# MCU.net
KiCad netlist of a schematic drawn in Altium Designer
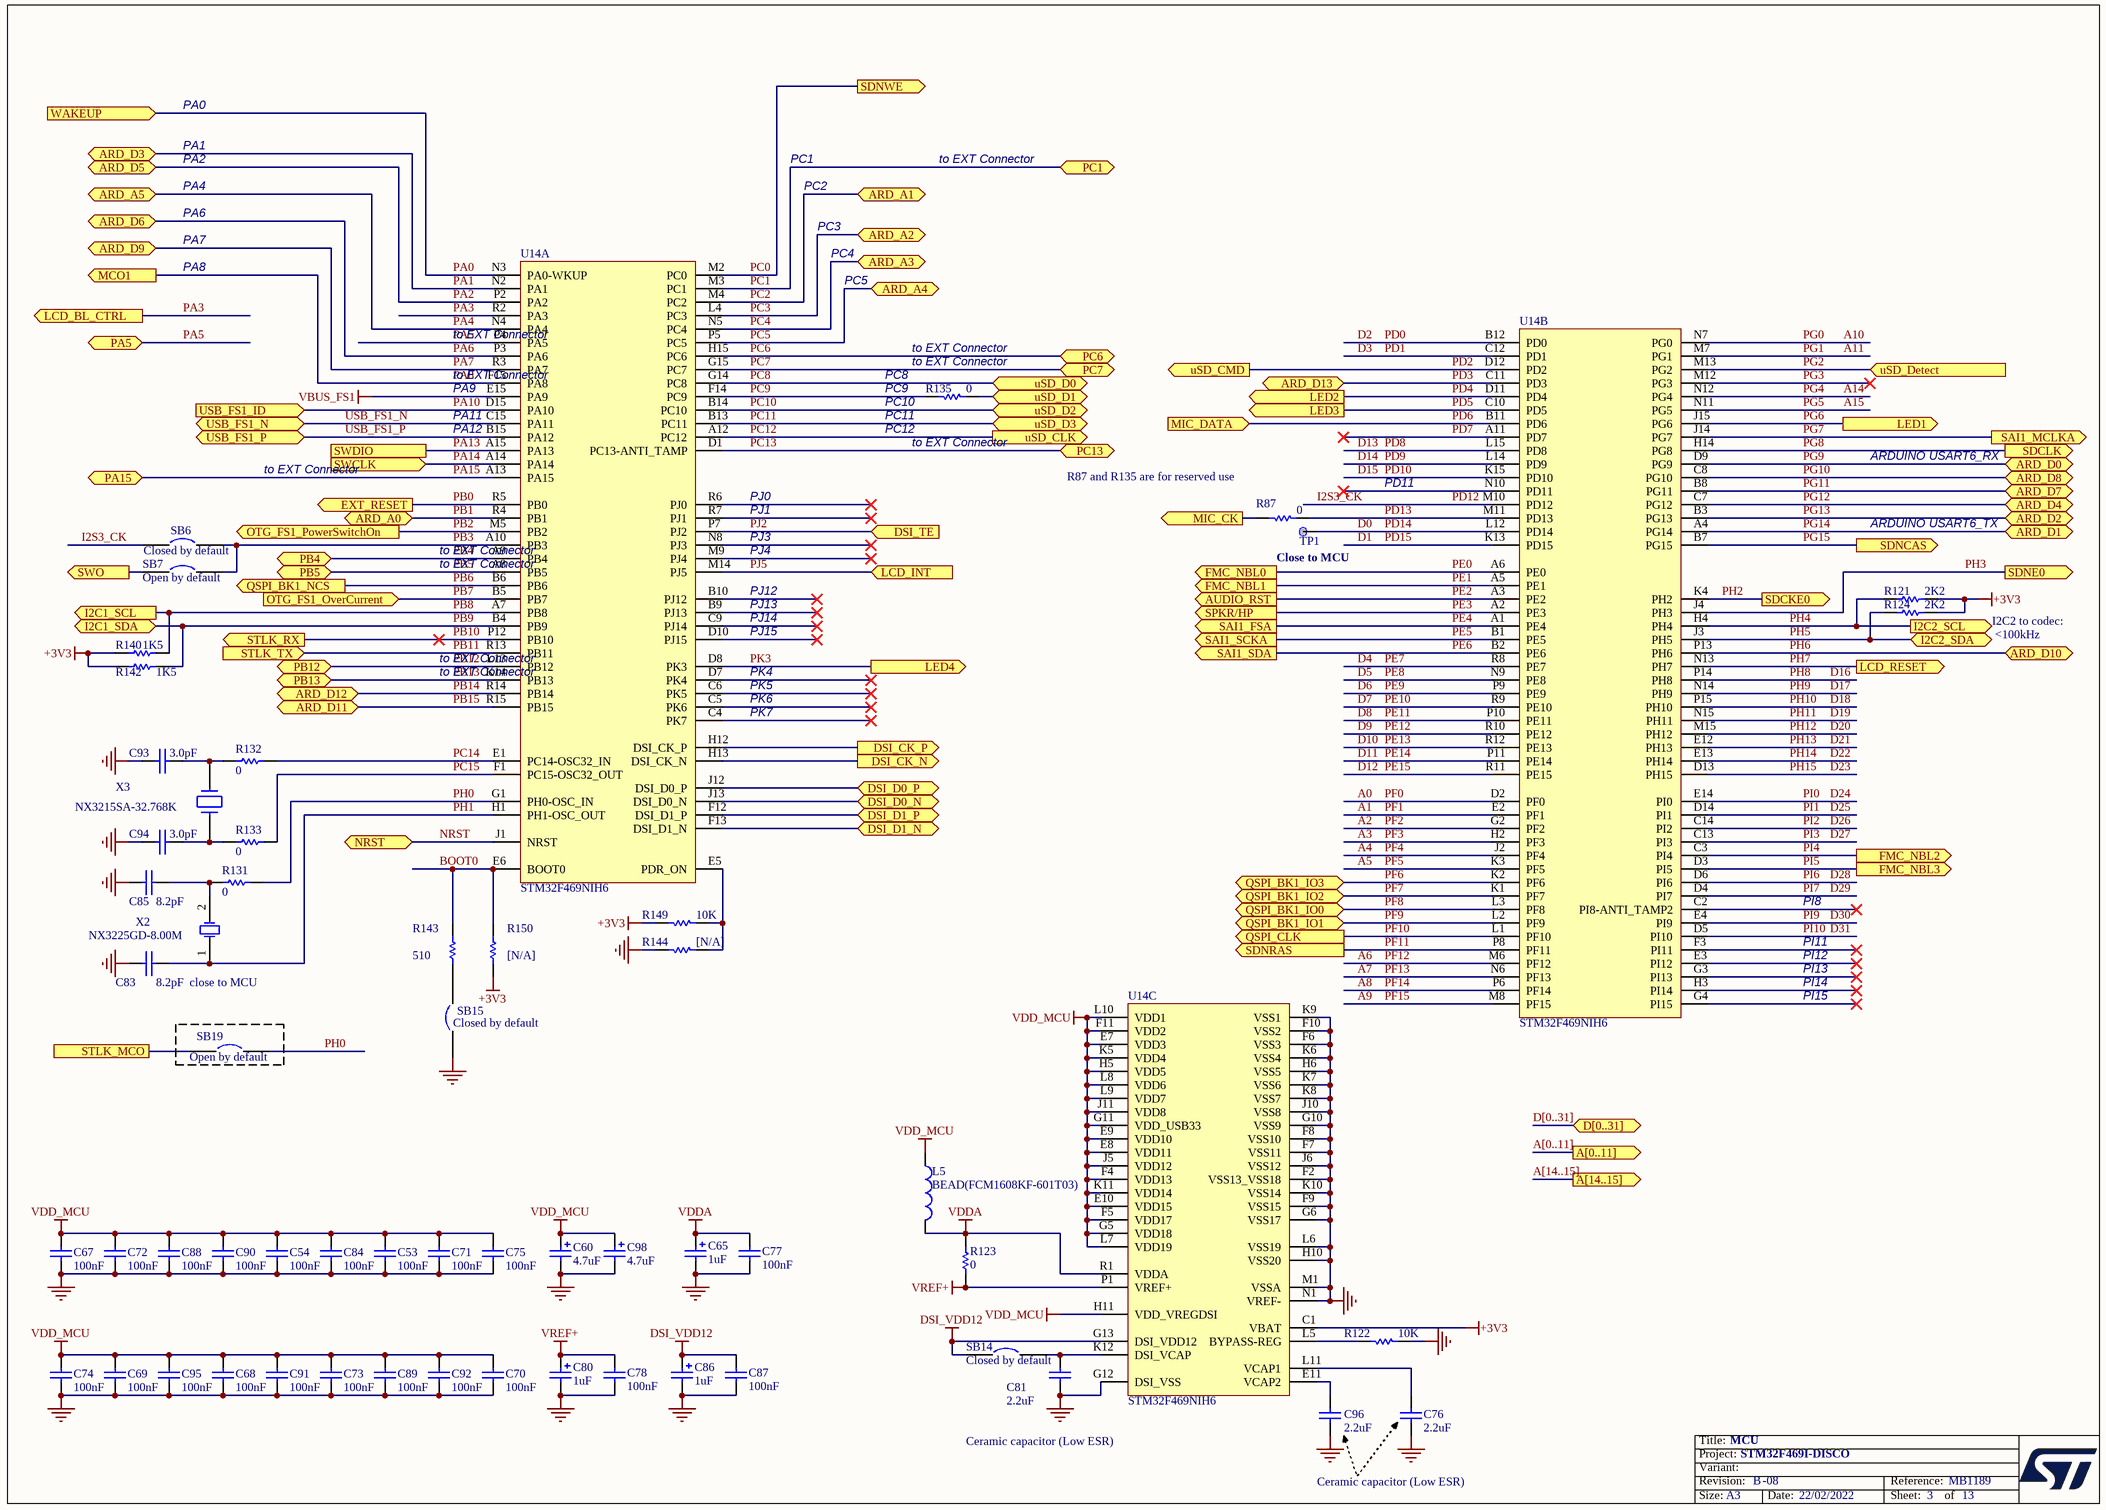
[diagram p0: MCU.SchDoc]

(export (version "E")
  (design (tool "Eeschema 10.0.6"))
  (components
    (comp (ref "C53")
      (value "100nF")
      (footprint "0402C")
      (description "Capacitor")
      (fields (field (name "PUBLISHER") "Altium Limited"))
      (libsource (lib "Miscellaneous Devices") (part "CAP"))
    )
    (comp (ref "C54")
      (value "100nF")
      (footprint "0402C")
      (description "Capacitor")
      (fields (field (name "PUBLISHER") "Altium Limited"))
      (libsource (lib "Miscellaneous Devices") (part "CAP"))
    )
    (comp (ref "C60")
      (value "4.7uF")
      (footprint "TAN-A")
      (description "Polarized Capacitor (Radial)")
      (fields (field (name "PUBLISHER") "Altium Limited"))
      (libsource (lib "Miscellaneous Devices") (part "Cap Pol1"))
    )
    (comp (ref "C65")
      (value "1uF")
      (footprint "TAN-A")
      (description "Polarized Capacitor (Radial)")
      (fields (field (name "PUBLISHER") "Altium Limited"))
      (libsource (lib "Miscellaneous Devices") (part "Cap Pol1"))
    )
    (comp (ref "C67")
      (value "100nF")
      (footprint "0402C")
      (description "Capacitor")
      (fields (field (name "PUBLISHER") "Altium Limited"))
      (libsource (lib "Miscellaneous Devices") (part "CAP"))
    )
    (comp (ref "C68")
      (value "100nF")
      (footprint "0402C")
      (description "Capacitor")
      (fields (field (name "PUBLISHER") "Altium Limited"))
      (libsource (lib "Miscellaneous Devices") (part "CAP"))
    )
    (comp (ref "C69")
      (value "100nF")
      (footprint "0402C")
      (description "Capacitor")
      (fields (field (name "PUBLISHER") "Altium Limited"))
      (libsource (lib "Miscellaneous Devices") (part "CAP"))
    )
    (comp (ref "C70")
      (value "100nF")
      (footprint "0402C")
      (description "Capacitor")
      (fields (field (name "PUBLISHER") "Altium Limited"))
      (libsource (lib "Miscellaneous Devices") (part "CAP"))
    )
    (comp (ref "C71")
      (value "100nF")
      (footprint "0402C")
      (description "Capacitor")
      (fields (field (name "PUBLISHER") "Altium Limited"))
      (libsource (lib "Miscellaneous Devices") (part "CAP"))
    )
    (comp (ref "C72")
      (value "100nF")
      (footprint "0402C")
      (description "Capacitor")
      (fields (field (name "PUBLISHER") "Altium Limited"))
      (libsource (lib "Miscellaneous Devices") (part "CAP"))
    )
    (comp (ref "C73")
      (value "100nF")
      (footprint "0402C")
      (description "Capacitor")
      (fields (field (name "PUBLISHER") "Altium Limited"))
      (libsource (lib "Miscellaneous Devices") (part "CAP"))
    )
    (comp (ref "C74")
      (value "100nF")
      (footprint "0402C")
      (description "Capacitor")
      (fields (field (name "PUBLISHER") "Altium Limited"))
      (libsource (lib "Miscellaneous Devices") (part "CAP"))
    )
    (comp (ref "C75")
      (value "100nF")
      (footprint "0402C")
      (description "Capacitor")
      (fields (field (name "PUBLISHER") "Altium Limited"))
      (libsource (lib "Miscellaneous Devices") (part "CAP"))
    )
    (comp (ref "C76")
      (value "2.2uF")
      (footprint "1206C")
      (description "Capacitor")
      (fields (field (name "PUBLISHER") "Altium Limited"))
      (libsource (lib "Miscellaneous Devices") (part "Cap"))
    )
    (comp (ref "C77")
      (value "100nF")
      (footprint "0402C")
      (description "Capacitor")
      (fields (field (name "PUBLISHER") "Altium Limited"))
      (libsource (lib "Miscellaneous Devices") (part "Cap"))
    )
    (comp (ref "C78")
      (value "100nF")
      (footprint "0402C")
      (description "Capacitor")
      (fields (field (name "PUBLISHER") "Altium Limited"))
      (libsource (lib "Miscellaneous Devices") (part "Cap"))
    )
    (comp (ref "C80")
      (value "1uF")
      (footprint "TAN-A")
      (description "Polarized Capacitor (Radial)")
      (fields (field (name "PUBLISHER") "Altium Limited"))
      (libsource (lib "Miscellaneous Devices") (part "Cap Pol1"))
    )
    (comp (ref "C81")
      (value "2.2uF")
      (footprint "1206C")
      (description "Capacitor")
      (fields (field (name "PUBLISHER") "Altium Limited"))
      (libsource (lib "Miscellaneous Devices") (part "Cap"))
    )
    (comp (ref "C83")
      (value "8.2pF")
      (footprint "0603C")
      (description "Capacitor")
      (libsource (lib "*") (part "CAP"))
    )
    (comp (ref "C84")
      (value "100nF")
      (footprint "0402C")
      (description "Capacitor")
      (fields (field (name "PUBLISHER") "Altium Limited"))
      (libsource (lib "Miscellaneous Devices") (part "CAP"))
    )
    (comp (ref "C85")
      (value "8.2pF")
      (footprint "0603C")
      (description "Capacitor")
      (libsource (lib "*") (part "CAP"))
    )
    (comp (ref "C86")
      (value "1uF")
      (footprint "TAN-A")
      (description "Polarized Capacitor (Radial)")
      (fields (field (name "PUBLISHER") "Altium Limited"))
      (libsource (lib "Miscellaneous Devices") (part "Cap Pol1"))
    )
    (comp (ref "C87")
      (value "100nF")
      (footprint "0402C")
      (description "Capacitor")
      (fields (field (name "PUBLISHER") "Altium Limited"))
      (libsource (lib "Miscellaneous Devices") (part "Cap"))
    )
    (comp (ref "C88")
      (value "100nF")
      (footprint "0402C")
      (description "Capacitor")
      (fields (field (name "PUBLISHER") "Altium Limited"))
      (libsource (lib "Miscellaneous Devices") (part "CAP"))
    )
    (comp (ref "C89")
      (value "100nF")
      (footprint "0402C")
      (description "Capacitor")
      (fields (field (name "PUBLISHER") "Altium Limited"))
      (libsource (lib "Miscellaneous Devices") (part "CAP"))
    )
    (comp (ref "C90")
      (value "100nF")
      (footprint "0402C")
      (description "Capacitor")
      (fields (field (name "PUBLISHER") "Altium Limited"))
      (libsource (lib "Miscellaneous Devices") (part "CAP"))
    )
    (comp (ref "C91")
      (value "100nF")
      (footprint "0402C")
      (description "Capacitor")
      (fields (field (name "PUBLISHER") "Altium Limited"))
      (libsource (lib "Miscellaneous Devices") (part "CAP"))
    )
    (comp (ref "C92")
      (value "100nF")
      (footprint "0402C")
      (description "Capacitor")
      (fields (field (name "PUBLISHER") "Altium Limited"))
      (libsource (lib "Miscellaneous Devices") (part "CAP"))
    )
    (comp (ref "C93")
      (value "3.0pF")
      (footprint "0603C")
      (description "Capacitor")
      (libsource (lib "") (part "CAP_1"))
    )
    (comp (ref "C94")
      (value "3.0pF")
      (footprint "0603C")
      (description "Capacitor")
      (libsource (lib "") (part "CAP_1"))
    )
    (comp (ref "C95")
      (value "100nF")
      (footprint "0402C")
      (description "Capacitor")
      (fields (field (name "PUBLISHER") "Altium Limited"))
      (libsource (lib "Miscellaneous Devices") (part "CAP"))
    )
    (comp (ref "C96")
      (value "2.2uF")
      (footprint "1206C")
      (description "Capacitor")
      (fields (field (name "PUBLISHER") "Altium Limited"))
      (libsource (lib "Miscellaneous Devices") (part "Cap"))
    )
    (comp (ref "C98")
      (value "4.7uF")
      (footprint "TAN-A")
      (description "Polarized Capacitor (Radial)")
      (fields (field (name "PUBLISHER") "Altium Limited"))
      (libsource (lib "Miscellaneous Devices") (part "Cap Pol1"))
    )
    (comp (ref "L5")
      (value "BEAD(FCM1608KF-601T03)")
      (footprint "0603L")
      (description "Inductor")
      (fields (field (name "PUBLISHER") "Altium Limited"))
      (libsource (lib "Miscellaneous Devices") (part "Inductor"))
    )
    (comp (ref "R87")
      (value "0")
      (footprint "0603R")
      (description "Resistor")
      (fields (field (name "PUBLISHER") "Altium Limited"))
      (libsource (lib "Miscellaneous Devices") (part "Res1"))
    )
    (comp (ref "R121")
      (value "2K2")
      (footprint "0603R")
      (description "Resistor")
      (fields (field (name "PUBLISHER") "Altium Limited"))
      (libsource (lib "") (part "Res1_1"))
    )
    (comp (ref "R122")
      (value "10K")
      (footprint "0402R")
      (description "Resistor")
      (fields (field (name "PUBLISHER") "Altium Limited"))
      (libsource (lib "") (part "Res1_1"))
    )
    (comp (ref "R123")
      (value "0")
      (footprint "0603R")
      (description "Resistor")
      (fields (field (name "PUBLISHER") "Altium Limited"))
      (libsource (lib "Miscellaneous Devices") (part "Res1"))
    )
    (comp (ref "R124")
      (value "2K2")
      (footprint "0603R")
      (description "Resistor")
      (fields (field (name "PUBLISHER") "Altium Limited"))
      (libsource (lib "") (part "Res1_1"))
    )
    (comp (ref "R131")
      (value "0")
      (footprint "0603R")
      (description "Resistor")
      (fields (field (name "PUBLISHER") "Altium Limited"))
      (libsource (lib "Miscellaneous Devices") (part "Res1"))
    )
    (comp (ref "R132")
      (value "0")
      (footprint "0603R")
      (description "Resistor")
      (fields (field (name "PUBLISHER") "Altium Limited"))
      (libsource (lib "") (part "Res1_1"))
    )
    (comp (ref "R133")
      (value "0")
      (footprint "0603R")
      (description "Resistor")
      (fields (field (name "PUBLISHER") "Altium Limited"))
      (libsource (lib "") (part "Res1_1"))
    )
    (comp (ref "R135")
      (value "0")
      (footprint "0603R")
      (description "Resistor")
      (fields (field (name "PUBLISHER") "Altium Limited"))
      (libsource (lib "Miscellaneous Devices") (part "Res1"))
    )
    (comp (ref "R140")
      (value "1K5")
      (footprint "0603R")
      (description "Resistor")
      (fields (field (name "PUBLISHER") "Altium Limited"))
      (libsource (lib "") (part "Res1_1"))
    )
    (comp (ref "R142")
      (value "1K5")
      (footprint "0603R")
      (description "Resistor")
      (fields (field (name "PUBLISHER") "Altium Limited"))
      (libsource (lib "") (part "Res1_1"))
    )
    (comp (ref "R143")
      (value "510")
      (footprint "0603R")
      (description "Resistor")
      (fields (field (name "PUBLISHER") "Altium Limited"))
      (libsource (lib "Miscellaneous Devices") (part "res1"))
    )
    (comp (ref "R144")
      (value "[N/A]")
      (footprint "0603R")
      (description "Resistor")
      (fields (field (name "PUBLISHER") "Altium Limited"))
      (libsource (lib "Miscellaneous Devices") (part "Res1"))
    )
    (comp (ref "R149")
      (value "10K")
      (footprint "0402R")
      (description "Resistor")
      (fields (field (name "PUBLISHER") "Altium Limited"))
      (libsource (lib "Miscellaneous Devices") (part "Res1"))
    )
    (comp (ref "R150")
      (value "[N/A]")
      (footprint "0603R")
      (description "Resistor")
      (fields (field (name "PUBLISHER") "Altium Limited"))
      (libsource (lib "Miscellaneous Devices") (part "res1"))
    )
    (comp (ref "SB6")
      (value "Closed by default")
      (footprint "SB_0603")
      (description "Circuit Breaker")
      (fields (field (name "PUBLISHER") "Altium Limited"))
      (libsource (lib "Miscellaneous Devices") (part "Circuit Breaker"))
    )
    (comp (ref "SB7")
      (value "Open by default")
      (footprint "SB_0603")
      (description "Circuit Breaker")
      (fields (field (name "PUBLISHER") "Altium Limited"))
      (libsource (lib "Miscellaneous Devices") (part "Circuit Breaker"))
    )
    (comp (ref "SB14")
      (value "Closed by default")
      (footprint "SB_0603")
      (description "Circuit Breaker")
      (fields (field (name "PUBLISHER") "Altium Limited"))
      (libsource (lib "Miscellaneous Devices") (part "Circuit Breaker"))
    )
    (comp (ref "SB15")
      (value "Closed by default")
      (footprint "SB_0603")
      (description "Circuit Breaker")
      (fields (field (name "PUBLISHER") "Altium Limited"))
      (libsource (lib "Miscellaneous Devices") (part "Circuit Breaker"))
    )
    (comp (ref "SB19")
      (value "Open by default")
      (footprint "SB_0603")
      (description "Circuit Breaker")
      (fields (field (name "PUBLISHER") "Altium Limited"))
      (libsource (lib "Miscellaneous Devices") (part "Circuit Breaker"))
    )
    (comp (ref "TP1") (value "TP") (footprint "TP_C40") (libsource (lib "Almos") (part "TP")))
    (comp (ref "U14")
      (value "STM32F469NIH6")
      (footprint "BGA216_0R8_13X13")
      (libsource (lib "MB1165") (part "Manta_Dragon_TFBGA216"))
    )
    (comp (ref "X2")
      (value "NX3225GD-8.00M")
      (footprint "XTAL_2SM_3R2X2R5_H1")
      (description "Crystal 8Mhz, 8pF, -+50PPM, SMD")
      (libsource (lib "MCD_TOOLS") (part "XTAL_8M_NX3225GD"))
    )
    (comp (ref "X3")
      (value "NX3215SA-32.768K")
      (footprint "XTAL_2SM_3R2X1R5")
      (description "Crystal 32.768kHz, 6pF, -+20PPM, R=50K, SMD")
      (libsource (lib "MCD_TOOLS") (part "XTAL_32K_NX3215SA"))
    )
  )
  (nets
    (net (code "1") (name "+3V3") (class "Default")
      (node (ref "R121") (pin "1") (pinfunction "1_1") (pintype "passive"))
      (node (ref "R124") (pin "1") (pinfunction "1_1") (pintype "passive"))
      (node (ref "R140") (pin "1") (pinfunction "1_1") (pintype "passive"))
      (node (ref "R142") (pin "1") (pinfunction "1_1") (pintype "passive"))
      (node (ref "R149") (pin "2") (pinfunction "2_2") (pintype "passive"))
      (node (ref "R150") (pin "2") (pinfunction "2_2") (pintype "passive"))
      (node (ref "U14") (pin "C1") (pinfunction "VBAT_C1") (pintype "passive"))
    )
    (net (code "2") (name "/A0") (class "Default")
      (node (ref "U14") (pin "D2") (pinfunction "PF0_D2") (pintype "passive"))
    )
    (net (code "3") (name "/A1") (class "Default")
      (node (ref "U14") (pin "E2") (pinfunction "PF1_E2") (pintype "passive"))
    )
    (net (code "4") (name "/A2") (class "Default")
      (node (ref "U14") (pin "G2") (pinfunction "PF2_G2") (pintype "passive"))
    )
    (net (code "5") (name "/A3") (class "Default")
      (node (ref "U14") (pin "H2") (pinfunction "PF3_H2") (pintype "passive"))
    )
    (net (code "6") (name "/A4") (class "Default")
      (node (ref "U14") (pin "J2") (pinfunction "PF4_J2") (pintype "passive"))
    )
    (net (code "7") (name "/A5") (class "Default")
      (node (ref "U14") (pin "K3") (pinfunction "PF5_K3") (pintype "passive"))
    )
    (net (code "8") (name "/A6") (class "Default")
      (node (ref "U14") (pin "M6") (pinfunction "PF12_M6") (pintype "passive"))
    )
    (net (code "9") (name "/A7") (class "Default")
      (node (ref "U14") (pin "N6") (pinfunction "PF13_N6") (pintype "passive"))
    )
    (net (code "10") (name "/A8") (class "Default")
      (node (ref "U14") (pin "P6") (pinfunction "PF14_P6") (pintype "passive"))
    )
    (net (code "11") (name "/A9") (class "Default")
      (node (ref "U14") (pin "M8") (pinfunction "PF15_M8") (pintype "passive"))
    )
    (net (code "12") (name "/A10") (class "Default")
      (node (ref "U14") (pin "N7") (pinfunction "PG0_N7") (pintype "passive"))
    )
    (net (code "13") (name "/A11") (class "Default")
      (node (ref "U14") (pin "M7") (pinfunction "PG1_M7") (pintype "passive"))
    )
    (net (code "14") (name "/A14") (class "Default")
      (node (ref "U14") (pin "N12") (pinfunction "PG4_N12") (pintype "passive"))
    )
    (net (code "15") (name "/A15") (class "Default")
      (node (ref "U14") (pin "N11") (pinfunction "PG5_N11") (pintype "passive"))
    )
    (net (code "18") (name "/BOOT0") (class "Default")
      (node (ref "R143") (pin "1") (pinfunction "1_1") (pintype "passive"))
      (node (ref "R150") (pin "1") (pinfunction "1_1") (pintype "passive"))
      (node (ref "U14") (pin "E6") (pinfunction "BOOT0_E6") (pintype "passive"))
    )
    (net (code "19") (name "/D0") (class "Default")
      (node (ref "TP1") (pin "1") (pinfunction "1_1") (pintype "passive"))
      (node (ref "U14") (pin "L12") (pinfunction "PD14_L12") (pintype "passive"))
    )
    (net (code "20") (name "/D1") (class "Default")
      (node (ref "U14") (pin "K13") (pinfunction "PD15_K13") (pintype "passive"))
    )
    (net (code "21") (name "/D2") (class "Default")
      (node (ref "U14") (pin "B12") (pinfunction "PD0_B12") (pintype "passive"))
    )
    (net (code "22") (name "/D3") (class "Default")
      (node (ref "U14") (pin "C12") (pinfunction "PD1_C12") (pintype "passive"))
    )
    (net (code "23") (name "/D4") (class "Default")
      (node (ref "U14") (pin "R8") (pinfunction "PE7_R8") (pintype "passive"))
    )
    (net (code "24") (name "/D5") (class "Default")
      (node (ref "U14") (pin "N9") (pinfunction "PE8_N9") (pintype "passive"))
    )
    (net (code "25") (name "/D6") (class "Default")
      (node (ref "U14") (pin "P9") (pinfunction "PE9_P9") (pintype "passive"))
    )
    (net (code "26") (name "/D7") (class "Default")
      (node (ref "U14") (pin "R9") (pinfunction "PE10_R9") (pintype "passive"))
    )
    (net (code "27") (name "/D8") (class "Default")
      (node (ref "U14") (pin "P10") (pinfunction "PE11_P10") (pintype "passive"))
    )
    (net (code "28") (name "/D9") (class "Default")
      (node (ref "U14") (pin "R10") (pinfunction "PE12_R10") (pintype "passive"))
    )
    (net (code "29") (name "/D10") (class "Default")
      (node (ref "U14") (pin "R12") (pinfunction "PE13_R12") (pintype "passive"))
    )
    (net (code "30") (name "/D11") (class "Default")
      (node (ref "U14") (pin "P11") (pinfunction "PE14_P11") (pintype "passive"))
    )
    (net (code "31") (name "/D12") (class "Default")
      (node (ref "U14") (pin "R11") (pinfunction "PE15_R11") (pintype "passive"))
    )
    (net (code "32") (name "/D13") (class "Default")
      (node (ref "U14") (pin "L15") (pinfunction "PD8_L15") (pintype "passive"))
    )
    (net (code "33") (name "/D14") (class "Default")
      (node (ref "U14") (pin "L14") (pinfunction "PD9_L14") (pintype "passive"))
    )
    (net (code "34") (name "/D15") (class "Default")
      (node (ref "U14") (pin "K15") (pinfunction "PD10_K15") (pintype "passive"))
    )
    (net (code "35") (name "/D16") (class "Default")
      (node (ref "U14") (pin "P14") (pinfunction "PH8_P14") (pintype "passive"))
    )
    (net (code "36") (name "/D17") (class "Default")
      (node (ref "U14") (pin "N14") (pinfunction "PH9_N14") (pintype "passive"))
    )
    (net (code "37") (name "/D18") (class "Default")
      (node (ref "U14") (pin "P15") (pinfunction "PH10_P15") (pintype "passive"))
    )
    (net (code "38") (name "/D19") (class "Default")
      (node (ref "U14") (pin "N15") (pinfunction "PH11_N15") (pintype "passive"))
    )
    (net (code "39") (name "/D20") (class "Default")
      (node (ref "U14") (pin "M15") (pinfunction "PH12_M15") (pintype "passive"))
    )
    (net (code "40") (name "/D21") (class "Default")
      (node (ref "U14") (pin "E12") (pinfunction "PH13_E12") (pintype "passive"))
    )
    (net (code "41") (name "/D22") (class "Default")
      (node (ref "U14") (pin "E13") (pinfunction "PH14_E13") (pintype "passive"))
    )
    (net (code "42") (name "/D23") (class "Default")
      (node (ref "U14") (pin "D13") (pinfunction "PH15_D13") (pintype "passive"))
    )
    (net (code "43") (name "/D24") (class "Default")
      (node (ref "U14") (pin "E14") (pinfunction "PI0_E14") (pintype "passive"))
    )
    (net (code "44") (name "/D25") (class "Default")
      (node (ref "U14") (pin "D14") (pinfunction "PI1_D14") (pintype "passive"))
    )
    (net (code "45") (name "/D26") (class "Default")
      (node (ref "U14") (pin "C14") (pinfunction "PI2_C14") (pintype "passive"))
    )
    (net (code "46") (name "/D27") (class "Default")
      (node (ref "U14") (pin "C13") (pinfunction "PI3_C13") (pintype "passive"))
    )
    (net (code "47") (name "/D28") (class "Default")
      (node (ref "U14") (pin "D6") (pinfunction "PI6_D6") (pintype "passive"))
    )
    (net (code "48") (name "/D29") (class "Default")
      (node (ref "U14") (pin "D4") (pinfunction "PI7_D4") (pintype "passive"))
    )
    (net (code "49") (name "/D30") (class "Default")
      (node (ref "U14") (pin "E4") (pinfunction "PI9_E4") (pintype "passive"))
    )
    (net (code "50") (name "/D31") (class "Default")
      (node (ref "U14") (pin "D5") (pinfunction "PI10_D5") (pintype "passive"))
    )
    (net (code "51") (name "/DSI_CK_N") (class "Default")
      (node (ref "U14") (pin "H13") (pinfunction "DSI_CK_N_H13") (pintype "passive"))
    )
    (net (code "52") (name "/DSI_CK_P") (class "Default")
      (node (ref "U14") (pin "H12") (pinfunction "DSI_CK_P_H12") (pintype "passive"))
    )
    (net (code "53") (name "/DSI_D0_N") (class "Default")
      (node (ref "U14") (pin "J13") (pinfunction "DSI_D0_N_J13") (pintype "passive"))
    )
    (net (code "54") (name "/DSI_D0_P") (class "Default")
      (node (ref "U14") (pin "J12") (pinfunction "DSI_D0_P_J12") (pintype "passive"))
    )
    (net (code "55") (name "/DSI_D1_N") (class "Default")
      (node (ref "U14") (pin "F13") (pinfunction "DSI_D1_N_F13") (pintype "passive"))
    )
    (net (code "56") (name "/DSI_D1_P") (class "Default")
      (node (ref "U14") (pin "F12") (pinfunction "DSI_D1_P_F12") (pintype "passive"))
    )
    (net (code "58") (name "/I2S3_CK") (class "Default")
      (node (ref "SB6") (pin "1") (pinfunction "1_1") (pintype "passive"))
      (node (ref "U14") (pin "M10") (pinfunction "PD12_M10") (pintype "passive"))
    )
    (net (code "59") (name "/MIC_CK") (class "Default")
      (node (ref "R87") (pin "1") (pinfunction "1_1") (pintype "passive"))
    )
    (net (code "60") (name "/NRST") (class "Default")
      (node (ref "U14") (pin "J1") (pinfunction "NRST_J1") (pintype "passive"))
    )
    (net (code "61") (name "/PA0") (class "Default")
      (node (ref "U14") (pin "N3") (pinfunction "PA0-WKUP_N3") (pintype "passive"))
    )
    (net (code "62") (name "/PA1") (class "Default")
      (node (ref "U14") (pin "N2") (pinfunction "PA1_N2") (pintype "passive"))
    )
    (net (code "63") (name "/PA2") (class "Default")
      (node (ref "U14") (pin "P2") (pinfunction "PA2_P2") (pintype "passive"))
    )
    (net (code "64") (name "/PA3") (class "Default")
      (node (ref "U14") (pin "R2") (pinfunction "PA3_R2") (pintype "passive"))
    )
    (net (code "65") (name "/PA4") (class "Default")
      (node (ref "U14") (pin "N4") (pinfunction "PA4_N4") (pintype "passive"))
    )
    (net (code "66") (name "/PA5") (class "Default")
      (node (ref "U14") (pin "P4") (pinfunction "PA5_P4") (pintype "passive"))
    )
    (net (code "67") (name "/PA6") (class "Default")
      (node (ref "U14") (pin "P3") (pinfunction "PA6_P3") (pintype "passive"))
    )
    (net (code "68") (name "/PA7") (class "Default")
      (node (ref "U14") (pin "R3") (pinfunction "PA7_R3") (pintype "passive"))
    )
    (net (code "69") (name "/PA8") (class "Default")
      (node (ref "U14") (pin "F15") (pinfunction "PA8_F15") (pintype "passive"))
    )
    (net (code "70") (name "/PA10") (class "Default")
      (node (ref "U14") (pin "D15") (pinfunction "PA10_D15") (pintype "passive"))
    )
    (net (code "71") (name "/PA13") (class "Default")
      (node (ref "U14") (pin "A15") (pinfunction "PA13_A15") (pintype "passive"))
    )
    (net (code "72") (name "/PA14") (class "Default")
      (node (ref "U14") (pin "A14") (pinfunction "PA14_A14") (pintype "passive"))
    )
    (net (code "73") (name "/PA15") (class "Default")
      (node (ref "U14") (pin "A13") (pinfunction "PA15_A13") (pintype "passive"))
    )
    (net (code "74") (name "/PB0") (class "Default")
      (node (ref "U14") (pin "R5") (pinfunction "PB0_R5") (pintype "passive"))
    )
    (net (code "75") (name "/PB1") (class "Default")
      (node (ref "U14") (pin "R4") (pinfunction "PB1_R4") (pintype "passive"))
    )
    (net (code "76") (name "/PB2") (class "Default")
      (node (ref "U14") (pin "M5") (pinfunction "PB2_M5") (pintype "passive"))
    )
    (net (code "77") (name "/PB3") (class "Default")
      (node (ref "SB6") (pin "2") (pinfunction "2_2") (pintype "passive"))
      (node (ref "SB7") (pin "2") (pinfunction "2_2") (pintype "passive"))
      (node (ref "U14") (pin "A10") (pinfunction "PB3_A10") (pintype "passive"))
    )
    (net (code "78") (name "/PB4") (class "Default")
      (node (ref "U14") (pin "A9") (pinfunction "PB4_A9") (pintype "passive"))
    )
    (net (code "79") (name "/PB5") (class "Default")
      (node (ref "U14") (pin "A8") (pinfunction "PB5_A8") (pintype "passive"))
    )
    (net (code "80") (name "/PB6") (class "Default")
      (node (ref "U14") (pin "B6") (pinfunction "PB6_B6") (pintype "passive"))
    )
    (net (code "81") (name "/PB7") (class "Default")
      (node (ref "U14") (pin "B5") (pinfunction "PB7_B5") (pintype "passive"))
    )
    (net (code "82") (name "/PB8") (class "Default")
      (node (ref "R140") (pin "2") (pinfunction "2_2") (pintype "passive"))
      (node (ref "U14") (pin "A7") (pinfunction "PB8_A7") (pintype "passive"))
    )
    (net (code "83") (name "/PB9") (class "Default")
      (node (ref "R142") (pin "2") (pinfunction "2_2") (pintype "passive"))
      (node (ref "U14") (pin "B4") (pinfunction "PB9_B4") (pintype "passive"))
    )
    (net (code "84") (name "/PB10") (class "Default")
      (node (ref "U14") (pin "P12") (pinfunction "PB10_P12") (pintype "passive"))
    )
    (net (code "85") (name "/PB11") (class "Default")
      (node (ref "U14") (pin "R13") (pinfunction "PB11_R13") (pintype "passive"))
    )
    (net (code "86") (name "/PB12") (class "Default")
      (node (ref "U14") (pin "L13") (pinfunction "PB12_L13") (pintype "passive"))
    )
    (net (code "87") (name "/PB13") (class "Default")
      (node (ref "U14") (pin "K14") (pinfunction "PB13_K14") (pintype "passive"))
    )
    (net (code "88") (name "/PB14") (class "Default")
      (node (ref "U14") (pin "R14") (pinfunction "PB14_R14") (pintype "passive"))
    )
    (net (code "89") (name "/PB15") (class "Default")
      (node (ref "U14") (pin "R15") (pinfunction "PB15_R15") (pintype "passive"))
    )
    (net (code "90") (name "/PC0") (class "Default")
      (node (ref "U14") (pin "M2") (pinfunction "PC0_M2") (pintype "passive"))
    )
    (net (code "91") (name "/PC1") (class "Default")
      (node (ref "U14") (pin "M3") (pinfunction "PC1_M3") (pintype "passive"))
    )
    (net (code "92") (name "/PC2") (class "Default")
      (node (ref "U14") (pin "M4") (pinfunction "PC2_M4") (pintype "passive"))
    )
    (net (code "93") (name "/PC3") (class "Default")
      (node (ref "U14") (pin "L4") (pinfunction "PC3_L4") (pintype "passive"))
    )
    (net (code "94") (name "/PC4") (class "Default")
      (node (ref "U14") (pin "N5") (pinfunction "PC4_N5") (pintype "passive"))
    )
    (net (code "95") (name "/PC5") (class "Default")
      (node (ref "U14") (pin "P5") (pinfunction "PC5_P5") (pintype "passive"))
    )
    (net (code "96") (name "/PC6") (class "Default")
      (node (ref "U14") (pin "H15") (pinfunction "PC6_H15") (pintype "passive"))
    )
    (net (code "97") (name "/PC7") (class "Default")
      (node (ref "U14") (pin "G15") (pinfunction "PC7_G15") (pintype "passive"))
    )
    (net (code "98") (name "/PC8") (class "Default")
      (node (ref "U14") (pin "G14") (pinfunction "PC8_G14") (pintype "passive"))
    )
    (net (code "99") (name "/PC9") (class "Default")
      (node (ref "R135") (pin "1") (pinfunction "1_1") (pintype "passive"))
      (node (ref "U14") (pin "F14") (pinfunction "PC9_F14") (pintype "passive"))
    )
    (net (code "100") (name "/PC10") (class "Default")
      (node (ref "U14") (pin "B14") (pinfunction "PC10_B14") (pintype "passive"))
    )
    (net (code "101") (name "/PC11") (class "Default")
      (node (ref "U14") (pin "B13") (pinfunction "PC11_B13") (pintype "passive"))
    )
    (net (code "102") (name "/PC12") (class "Default")
      (node (ref "U14") (pin "A12") (pinfunction "PC12_A12") (pintype "passive"))
    )
    (net (code "103") (name "/PC13") (class "Default")
      (node (ref "U14") (pin "D1") (pinfunction "PC13-ANTI_TAMP_D1") (pintype "passive"))
    )
    (net (code "104") (name "/PC14") (class "Default")
      (node (ref "R132") (pin "2") (pinfunction "2_2") (pintype "passive"))
      (node (ref "U14") (pin "E1") (pinfunction "PC14-OSC32_IN_E1") (pintype "passive"))
    )
    (net (code "105") (name "/PC15") (class "Default")
      (node (ref "R133") (pin "2") (pinfunction "2_2") (pintype "passive"))
      (node (ref "U14") (pin "F1") (pinfunction "PC15-OSC32_OUT_F1") (pintype "passive"))
    )
    (net (code "106") (name "/PD2") (class "Default")
      (node (ref "U14") (pin "D12") (pinfunction "PD2_D12") (pintype "passive"))
    )
    (net (code "107") (name "/PD3") (class "Default")
      (node (ref "U14") (pin "C11") (pinfunction "PD3_C11") (pintype "passive"))
    )
    (net (code "108") (name "/PD4") (class "Default")
      (node (ref "U14") (pin "D11") (pinfunction "PD4_D11") (pintype "passive"))
    )
    (net (code "109") (name "/PD5") (class "Default")
      (node (ref "U14") (pin "C10") (pinfunction "PD5_C10") (pintype "passive"))
    )
    (net (code "110") (name "/PD6") (class "Default")
      (node (ref "U14") (pin "B11") (pinfunction "PD6_B11") (pintype "passive"))
    )
    (net (code "111") (name "/PD7") (class "Default")
      (node (ref "U14") (pin "A11") (pinfunction "PD7_A11") (pintype "passive+no_connect"))
    )
    (net (code "112") (name "/PD13") (class "Default")
      (node (ref "R87") (pin "2") (pinfunction "2_2") (pintype "passive"))
      (node (ref "U14") (pin "M11") (pinfunction "PD13_M11") (pintype "passive"))
    )
    (net (code "113") (name "/PE0") (class "Default")
      (node (ref "U14") (pin "A6") (pinfunction "PE0_A6") (pintype "passive"))
    )
    (net (code "114") (name "/PE1") (class "Default")
      (node (ref "U14") (pin "A5") (pinfunction "PE1_A5") (pintype "passive"))
    )
    (net (code "115") (name "/PE2") (class "Default")
      (node (ref "U14") (pin "A3") (pinfunction "PE2_A3") (pintype "passive"))
    )
    (net (code "116") (name "/PE3") (class "Default")
      (node (ref "U14") (pin "A2") (pinfunction "PE3_A2") (pintype "passive"))
    )
    (net (code "117") (name "/PE4") (class "Default")
      (node (ref "U14") (pin "A1") (pinfunction "PE4_A1") (pintype "passive"))
    )
    (net (code "118") (name "/PE5") (class "Default")
      (node (ref "U14") (pin "B1") (pinfunction "PE5_B1") (pintype "passive"))
    )
    (net (code "119") (name "/PE6") (class "Default")
      (node (ref "U14") (pin "B2") (pinfunction "PE6_B2") (pintype "passive"))
    )
    (net (code "120") (name "/PF6") (class "Default")
      (node (ref "U14") (pin "K2") (pinfunction "PF6_K2") (pintype "passive"))
    )
    (net (code "121") (name "/PF7") (class "Default")
      (node (ref "U14") (pin "K1") (pinfunction "PF7_K1") (pintype "passive"))
    )
    (net (code "122") (name "/PF8") (class "Default")
      (node (ref "U14") (pin "L3") (pinfunction "PF8_L3") (pintype "passive"))
    )
    (net (code "123") (name "/PF9") (class "Default")
      (node (ref "U14") (pin "L2") (pinfunction "PF9_L2") (pintype "passive"))
    )
    (net (code "124") (name "/PF10") (class "Default")
      (node (ref "U14") (pin "L1") (pinfunction "PF10_L1") (pintype "passive"))
    )
    (net (code "125") (name "/PF11") (class "Default")
      (node (ref "U14") (pin "P8") (pinfunction "PF11_P8") (pintype "passive"))
    )
    (net (code "126") (name "/PG2") (class "Default")
      (node (ref "U14") (pin "M13") (pinfunction "PG2_M13") (pintype "passive"))
    )
    (net (code "127") (name "/PG3") (class "Default")
      (node (ref "U14") (pin "M12") (pinfunction "PG3_M12") (pintype "passive+no_connect"))
    )
    (net (code "128") (name "/PG6") (class "Default")
      (node (ref "U14") (pin "J15") (pinfunction "PG6_J15") (pintype "passive"))
    )
    (net (code "129") (name "/PG7") (class "Default")
      (node (ref "U14") (pin "J14") (pinfunction "PG7_J14") (pintype "passive"))
    )
    (net (code "130") (name "/PG8") (class "Default")
      (node (ref "U14") (pin "H14") (pinfunction "PG8_H14") (pintype "passive"))
    )
    (net (code "131") (name "/PG9") (class "Default")
      (node (ref "U14") (pin "D9") (pinfunction "PG9_D9") (pintype "passive"))
    )
    (net (code "132") (name "/PG10") (class "Default")
      (node (ref "U14") (pin "C8") (pinfunction "PG10_C8") (pintype "passive"))
    )
    (net (code "133") (name "/PG11") (class "Default")
      (node (ref "U14") (pin "B8") (pinfunction "PG11_B8") (pintype "passive"))
    )
    (net (code "134") (name "/PG12") (class "Default")
      (node (ref "U14") (pin "C7") (pinfunction "PG12_C7") (pintype "passive"))
    )
    (net (code "135") (name "/PG13") (class "Default")
      (node (ref "U14") (pin "B3") (pinfunction "PG13_B3") (pintype "passive"))
    )
    (net (code "136") (name "/PG14") (class "Default")
      (node (ref "U14") (pin "A4") (pinfunction "PG14_A4") (pintype "passive"))
    )
    (net (code "137") (name "/PG15") (class "Default")
      (node (ref "U14") (pin "B7") (pinfunction "PG15_B7") (pintype "passive"))
    )
    (net (code "138") (name "/PH0") (class "Default")
      (node (ref "R131") (pin "1") (pinfunction "1_1") (pintype "passive"))
      (node (ref "SB19") (pin "2") (pinfunction "2_2") (pintype "passive"))
      (node (ref "U14") (pin "G1") (pinfunction "PH0-OSC_IN_G1") (pintype "passive"))
    )
    (net (code "139") (name "/PH1") (class "Default")
      (node (ref "C83") (pin "1") (pinfunction "1_1") (pintype "passive"))
      (node (ref "U14") (pin "H1") (pinfunction "PH1-OSC_OUT_H1") (pintype "passive"))
      (node (ref "X2") (pin "1") (pinfunction "OSC1_1") (pintype "passive"))
    )
    (net (code "140") (name "/PH2") (class "Default")
      (node (ref "U14") (pin "K4") (pinfunction "PH2_K4") (pintype "passive"))
    )
    (net (code "141") (name "/PH3") (class "Default")
      (node (ref "U14") (pin "J4") (pinfunction "PH3_J4") (pintype "passive"))
    )
    (net (code "142") (name "/PH4") (class "Default")
      (node (ref "R121") (pin "2") (pinfunction "2_2") (pintype "passive"))
      (node (ref "U14") (pin "H4") (pinfunction "PH4_H4") (pintype "passive"))
    )
    (net (code "143") (name "/PH5") (class "Default")
      (node (ref "R124") (pin "2") (pinfunction "2_2") (pintype "passive"))
      (node (ref "U14") (pin "J3") (pinfunction "PH5_J3") (pintype "passive"))
    )
    (net (code "144") (name "/PH6") (class "Default")
      (node (ref "U14") (pin "P13") (pinfunction "PH6_P13") (pintype "passive"))
    )
    (net (code "145") (name "/PH7") (class "Default")
      (node (ref "U14") (pin "N13") (pinfunction "PH7_N13") (pintype "passive"))
    )
    (net (code "146") (name "/PI4") (class "Default")
      (node (ref "U14") (pin "C3") (pinfunction "PI4_C3") (pintype "passive"))
    )
    (net (code "147") (name "/PI5") (class "Default")
      (node (ref "U14") (pin "D3") (pinfunction "PI5_D3") (pintype "passive"))
    )
    (net (code "148") (name "/PJ2") (class "Default")
      (node (ref "U14") (pin "P7") (pinfunction "PJ2_P7") (pintype "passive"))
    )
    (net (code "149") (name "/PJ5") (class "Default")
      (node (ref "U14") (pin "M14") (pinfunction "PJ5_M14") (pintype "passive"))
    )
    (net (code "150") (name "/PK3") (class "Default")
      (node (ref "U14") (pin "D8") (pinfunction "PK3_D8") (pintype "passive"))
    )
    (net (code "151") (name "/STLK_MCO") (class "Default")
      (node (ref "SB19") (pin "1") (pinfunction "1_1") (pintype "passive"))
    )
    (net (code "152") (name "/SWO") (class "Default")
      (node (ref "SB7") (pin "1") (pinfunction "1_1") (pintype "passive"))
    )
    (net (code "153") (name "/USB_FS1_N") (class "Default")
      (node (ref "U14") (pin "C15") (pinfunction "PA11_C15") (pintype "passive"))
    )
    (net (code "154") (name "/USB_FS1_P") (class "Default")
      (node (ref "U14") (pin "B15") (pinfunction "PA12_B15") (pintype "passive"))
    )
    (net (code "155") (name "/uSD_D1") (class "Default")
      (node (ref "R135") (pin "2") (pinfunction "2_2") (pintype "passive"))
    )
    (net (code "156") (name "DSI_VDD12") (class "Default")
      (node (ref "C86") (pin "1") (pinfunction "1_1") (pintype "passive"))
      (node (ref "C87") (pin "2") (pinfunction "2_2") (pintype "passive"))
      (node (ref "SB14") (pin "1") (pinfunction "1_1") (pintype "passive"))
      (node (ref "U14") (pin "G13") (pinfunction "DSI_VDD12_G13") (pintype "passive"))
    )
    (net (code "157") (name "GND") (class "Default")
      (node (ref "C53") (pin "2") (pinfunction "2_2") (pintype "passive"))
      (node (ref "C54") (pin "2") (pinfunction "2_2") (pintype "passive"))
      (node (ref "C60") (pin "2") (pinfunction "2_2") (pintype "passive"))
      (node (ref "C65") (pin "2") (pinfunction "2_2") (pintype "passive"))
      (node (ref "C67") (pin "2") (pinfunction "2_2") (pintype "passive"))
      (node (ref "C68") (pin "2") (pinfunction "2_2") (pintype "passive"))
      (node (ref "C69") (pin "2") (pinfunction "2_2") (pintype "passive"))
      (node (ref "C70") (pin "2") (pinfunction "2_2") (pintype "passive"))
      (node (ref "C71") (pin "2") (pinfunction "2_2") (pintype "passive"))
      (node (ref "C72") (pin "2") (pinfunction "2_2") (pintype "passive"))
      (node (ref "C73") (pin "2") (pinfunction "2_2") (pintype "passive"))
      (node (ref "C74") (pin "2") (pinfunction "2_2") (pintype "passive"))
      (node (ref "C75") (pin "2") (pinfunction "2_2") (pintype "passive"))
      (node (ref "C76") (pin "2") (pinfunction "2_2") (pintype "passive"))
      (node (ref "C77") (pin "1") (pinfunction "1_1") (pintype "passive"))
      (node (ref "C78") (pin "1") (pinfunction "1_1") (pintype "passive"))
      (node (ref "C80") (pin "2") (pinfunction "2_2") (pintype "passive"))
      (node (ref "C81") (pin "2") (pinfunction "2_2") (pintype "passive"))
      (node (ref "C83") (pin "2") (pinfunction "2_2") (pintype "passive"))
      (node (ref "C84") (pin "2") (pinfunction "2_2") (pintype "passive"))
      (node (ref "C85") (pin "2") (pinfunction "2_2") (pintype "passive"))
      (node (ref "C86") (pin "2") (pinfunction "2_2") (pintype "passive"))
      (node (ref "C87") (pin "1") (pinfunction "1_1") (pintype "passive"))
      (node (ref "C88") (pin "2") (pinfunction "2_2") (pintype "passive"))
      (node (ref "C89") (pin "2") (pinfunction "2_2") (pintype "passive"))
      (node (ref "C90") (pin "2") (pinfunction "2_2") (pintype "passive"))
      (node (ref "C91") (pin "2") (pinfunction "2_2") (pintype "passive"))
      (node (ref "C92") (pin "2") (pinfunction "2_2") (pintype "passive"))
      (node (ref "C93") (pin "2") (pinfunction "2_2") (pintype "passive"))
      (node (ref "C94") (pin "2") (pinfunction "2_2") (pintype "passive"))
      (node (ref "C95") (pin "2") (pinfunction "2_2") (pintype "passive"))
      (node (ref "C96") (pin "2") (pinfunction "2_2") (pintype "passive"))
      (node (ref "C98") (pin "2") (pinfunction "2_2") (pintype "passive"))
      (node (ref "R122") (pin "1") (pinfunction "1_1") (pintype "passive"))
      (node (ref "R144") (pin "2") (pinfunction "2_2") (pintype "passive"))
      (node (ref "SB15") (pin "1") (pinfunction "1_1") (pintype "passive"))
      (node (ref "U14") (pin "F10") (pinfunction "VSS2_F10") (pintype "passive"))
      (node (ref "U14") (pin "F2") (pinfunction "VSS13_VSS18_F2") (pintype "passive"))
      (node (ref "U14") (pin "F6") (pinfunction "VSS3_F6") (pintype "passive"))
      (node (ref "U14") (pin "F7") (pinfunction "VSS11_F7") (pintype "passive"))
      (node (ref "U14") (pin "F8") (pinfunction "VSS10_F8") (pintype "passive"))
      (node (ref "U14") (pin "F9") (pinfunction "VSS15_F9") (pintype "passive"))
      (node (ref "U14") (pin "G10") (pinfunction "VSS9_G10") (pintype "passive"))
      (node (ref "U14") (pin "G12") (pinfunction "DSI_VSS_G12") (pintype "passive"))
      (node (ref "U14") (pin "G6") (pinfunction "VSS17_G6") (pintype "passive"))
      (node (ref "U14") (pin "H10") (pinfunction "VSS20_H10") (pintype "passive"))
      (node (ref "U14") (pin "H6") (pinfunction "VSS5_H6") (pintype "passive"))
      (node (ref "U14") (pin "J10") (pinfunction "VSS8_J10") (pintype "passive"))
      (node (ref "U14") (pin "J6") (pinfunction "VSS12_J6") (pintype "passive"))
      (node (ref "U14") (pin "K10") (pinfunction "VSS14_K10") (pintype "passive"))
      (node (ref "U14") (pin "K6") (pinfunction "VSS4_K6") (pintype "passive"))
      (node (ref "U14") (pin "K7") (pinfunction "VSS6_K7") (pintype "passive"))
      (node (ref "U14") (pin "K8") (pinfunction "VSS7_K8") (pintype "passive"))
      (node (ref "U14") (pin "K9") (pinfunction "VSS1_K9") (pintype "passive"))
      (node (ref "U14") (pin "L6") (pinfunction "VSS19_L6") (pintype "passive"))
      (node (ref "U14") (pin "M1") (pinfunction "VSSA_M1") (pintype "passive"))
      (node (ref "U14") (pin "N1") (pinfunction "VREF-_N1") (pintype "passive"))
    )
    (net (code "158") (name "Net-(C93-Pad1)") (class "Default")
      (node (ref "C93") (pin "1") (pinfunction "1_1") (pintype "passive"))
      (node (ref "R132") (pin "1") (pinfunction "1_1") (pintype "passive"))
      (node (ref "X3") (pin "1") (pinfunction "1_1") (pintype "passive"))
    )
    (net (code "159") (name "Net-(C94-Pad1)") (class "Default")
      (node (ref "C94") (pin "1") (pinfunction "1_1") (pintype "passive"))
      (node (ref "R133") (pin "1") (pinfunction "1_1") (pintype "passive"))
      (node (ref "X3") (pin "2") (pinfunction "2_2") (pintype "passive"))
    )
    (net (code "160") (name "Net-(R143-Pad2)") (class "Default")
      (node (ref "R143") (pin "2") (pinfunction "2_2") (pintype "passive"))
      (node (ref "SB15") (pin "2") (pinfunction "2_2") (pintype "passive"))
    )
    (net (code "161") (name "Net-(U14A-PDR_ON)") (class "Default")
      (node (ref "R144") (pin "1") (pinfunction "1_1") (pintype "passive"))
      (node (ref "R149") (pin "1") (pinfunction "1_1") (pintype "passive"))
      (node (ref "U14") (pin "E5") (pinfunction "PDR_ON_E5") (pintype "passive"))
    )
    (net (code "162") (name "Net-(U14C-BYPASS-REG)") (class "Default")
      (node (ref "R122") (pin "2") (pinfunction "2_2") (pintype "passive"))
      (node (ref "U14") (pin "L5") (pinfunction "BYPASS-REG_L5") (pintype "passive"))
    )
    (net (code "163") (name "Net-(U14C-DSI_VCAP)") (class "Default")
      (node (ref "C81") (pin "1") (pinfunction "1_1") (pintype "passive"))
      (node (ref "SB14") (pin "2") (pinfunction "2_2") (pintype "passive"))
      (node (ref "U14") (pin "K12") (pinfunction "DSI_VCAP_K12") (pintype "passive"))
    )
    (net (code "164") (name "Net-(U14C-VCAP1)") (class "Default")
      (node (ref "C76") (pin "1") (pinfunction "1_1") (pintype "passive"))
      (node (ref "U14") (pin "L11") (pinfunction "VCAP1_L11") (pintype "passive"))
    )
    (net (code "165") (name "Net-(U14C-VCAP2)") (class "Default")
      (node (ref "C96") (pin "1") (pinfunction "1_1") (pintype "passive"))
      (node (ref "U14") (pin "E11") (pinfunction "VCAP2_E11") (pintype "passive"))
    )
    (net (code "166") (name "Net-(X2-OSC2)") (class "Default")
      (node (ref "C85") (pin "1") (pinfunction "1_1") (pintype "passive"))
      (node (ref "R131") (pin "2") (pinfunction "2_2") (pintype "passive"))
      (node (ref "X2") (pin "2") (pinfunction "OSC2_2") (pintype "passive"))
    )
    (net (code "167") (name "VBUS_FS1") (class "Default")
      (node (ref "U14") (pin "E15") (pinfunction "PA9_E15") (pintype "passive"))
    )
    (net (code "168") (name "VDDA") (class "Default")
      (node (ref "C65") (pin "1") (pinfunction "1_1") (pintype "passive"))
      (node (ref "C77") (pin "2") (pinfunction "2_2") (pintype "passive"))
      (node (ref "L5") (pin "2") (pinfunction "2_2") (pintype "passive"))
      (node (ref "R123") (pin "1") (pinfunction "1_1") (pintype "passive"))
      (node (ref "U14") (pin "R1") (pinfunction "VDDA_R1") (pintype "passive"))
    )
    (net (code "169") (name "VDD_MCU") (class "Default")
      (node (ref "C53") (pin "1") (pinfunction "1_1") (pintype "passive"))
      (node (ref "C54") (pin "1") (pinfunction "1_1") (pintype "passive"))
      (node (ref "C60") (pin "1") (pinfunction "1_1") (pintype "passive"))
      (node (ref "C67") (pin "1") (pinfunction "1_1") (pintype "passive"))
      (node (ref "C68") (pin "1") (pinfunction "1_1") (pintype "passive"))
      (node (ref "C69") (pin "1") (pinfunction "1_1") (pintype "passive"))
      (node (ref "C70") (pin "1") (pinfunction "1_1") (pintype "passive"))
      (node (ref "C71") (pin "1") (pinfunction "1_1") (pintype "passive"))
      (node (ref "C72") (pin "1") (pinfunction "1_1") (pintype "passive"))
      (node (ref "C73") (pin "1") (pinfunction "1_1") (pintype "passive"))
      (node (ref "C74") (pin "1") (pinfunction "1_1") (pintype "passive"))
      (node (ref "C75") (pin "1") (pinfunction "1_1") (pintype "passive"))
      (node (ref "C84") (pin "1") (pinfunction "1_1") (pintype "passive"))
      (node (ref "C88") (pin "1") (pinfunction "1_1") (pintype "passive"))
      (node (ref "C89") (pin "1") (pinfunction "1_1") (pintype "passive"))
      (node (ref "C90") (pin "1") (pinfunction "1_1") (pintype "passive"))
      (node (ref "C91") (pin "1") (pinfunction "1_1") (pintype "passive"))
      (node (ref "C92") (pin "1") (pinfunction "1_1") (pintype "passive"))
      (node (ref "C95") (pin "1") (pinfunction "1_1") (pintype "passive"))
      (node (ref "C98") (pin "1") (pinfunction "1_1") (pintype "passive"))
      (node (ref "L5") (pin "1") (pinfunction "1_1") (pintype "passive"))
      (node (ref "U14") (pin "E10") (pinfunction "VDD15_E10") (pintype "passive"))
      (node (ref "U14") (pin "E7") (pinfunction "VDD3_E7") (pintype "passive"))
      (node (ref "U14") (pin "E8") (pinfunction "VDD11_E8") (pintype "passive"))
      (node (ref "U14") (pin "E9") (pinfunction "VDD10_E9") (pintype "passive"))
      (node (ref "U14") (pin "F11") (pinfunction "VDD2_F11") (pintype "passive"))
      (node (ref "U14") (pin "F4") (pinfunction "VDD13_F4") (pintype "passive"))
      (node (ref "U14") (pin "F5") (pinfunction "VDD17_F5") (pintype "passive"))
      (node (ref "U14") (pin "G11") (pinfunction "VDD_USB33_G11") (pintype "passive"))
      (node (ref "U14") (pin "G5") (pinfunction "VDD18_G5") (pintype "passive"))
      (node (ref "U14") (pin "H11") (pinfunction "VDD_VREGDSI_H11") (pintype "passive"))
      (node (ref "U14") (pin "H5") (pinfunction "VDD5_H5") (pintype "passive"))
      (node (ref "U14") (pin "J11") (pinfunction "VDD8_J11") (pintype "passive"))
      (node (ref "U14") (pin "J5") (pinfunction "VDD12_J5") (pintype "passive"))
      (node (ref "U14") (pin "K11") (pinfunction "VDD14_K11") (pintype "passive"))
      (node (ref "U14") (pin "K5") (pinfunction "VDD4_K5") (pintype "passive"))
      (node (ref "U14") (pin "L10") (pinfunction "VDD1_L10") (pintype "passive"))
      (node (ref "U14") (pin "L7") (pinfunction "VDD19_L7") (pintype "passive"))
      (node (ref "U14") (pin "L8") (pinfunction "VDD6_L8") (pintype "passive"))
      (node (ref "U14") (pin "L9") (pinfunction "VDD7_L9") (pintype "passive"))
    )
    (net (code "170") (name "VREF+") (class "Default")
      (node (ref "C78") (pin "2") (pinfunction "2_2") (pintype "passive"))
      (node (ref "C80") (pin "1") (pinfunction "1_1") (pintype "passive"))
      (node (ref "R123") (pin "2") (pinfunction "2_2") (pintype "passive"))
      (node (ref "U14") (pin "P1") (pinfunction "VREF+_P1") (pintype "passive"))
    )
    (net (code "171") (name "unconnected-(U14A-PJ0-PadR6)") (class "Default")
      (node (ref "U14") (pin "R6") (pinfunction "PJ0_R6") (pintype "passive+no_connect"))
    )
    (net (code "172") (name "unconnected-(U14A-PJ1-PadR7)") (class "Default")
      (node (ref "U14") (pin "R7") (pinfunction "PJ1_R7") (pintype "passive+no_connect"))
    )
    (net (code "173") (name "unconnected-(U14A-PJ3-PadN8)") (class "Default")
      (node (ref "U14") (pin "N8") (pinfunction "PJ3_N8") (pintype "passive+no_connect"))
    )
    (net (code "174") (name "unconnected-(U14A-PJ4-PadM9)") (class "Default")
      (node (ref "U14") (pin "M9") (pinfunction "PJ4_M9") (pintype "passive+no_connect"))
    )
    (net (code "175") (name "unconnected-(U14A-PJ12-PadB10)") (class "Default")
      (node (ref "U14") (pin "B10") (pinfunction "PJ12_B10") (pintype "passive+no_connect"))
    )
    (net (code "176") (name "unconnected-(U14A-PJ13-PadB9)") (class "Default")
      (node (ref "U14") (pin "B9") (pinfunction "PJ13_B9") (pintype "passive+no_connect"))
    )
    (net (code "177") (name "unconnected-(U14A-PJ14-PadC9)") (class "Default")
      (node (ref "U14") (pin "C9") (pinfunction "PJ14_C9") (pintype "passive+no_connect"))
    )
    (net (code "178") (name "unconnected-(U14A-PJ15-PadD10)") (class "Default")
      (node (ref "U14") (pin "D10") (pinfunction "PJ15_D10") (pintype "passive+no_connect"))
    )
    (net (code "179") (name "unconnected-(U14A-PK4-PadD7)") (class "Default")
      (node (ref "U14") (pin "D7") (pinfunction "PK4_D7") (pintype "passive+no_connect"))
    )
    (net (code "180") (name "unconnected-(U14A-PK5-PadC6)") (class "Default")
      (node (ref "U14") (pin "C6") (pinfunction "PK5_C6") (pintype "passive+no_connect"))
    )
    (net (code "181") (name "unconnected-(U14A-PK6-PadC5)") (class "Default")
      (node (ref "U14") (pin "C5") (pinfunction "PK6_C5") (pintype "passive+no_connect"))
    )
    (net (code "182") (name "unconnected-(U14A-PK7-PadC4)") (class "Default")
      (node (ref "U14") (pin "C4") (pinfunction "PK7_C4") (pintype "passive+no_connect"))
    )
    (net (code "183") (name "unconnected-(U14B-PD11-PadN10)") (class "Default")
      (node (ref "U14") (pin "N10") (pinfunction "PD11_N10") (pintype "passive+no_connect"))
    )
    (net (code "184") (name "unconnected-(U14B-PI8-ANTI_TAMP2-PadC2)") (class "Default")
      (node (ref "U14") (pin "C2") (pinfunction "PI8-ANTI_TAMP2_C2") (pintype "passive+no_connect"))
    )
    (net (code "185") (name "unconnected-(U14B-PI11-PadF3)") (class "Default")
      (node (ref "U14") (pin "F3") (pinfunction "PI11_F3") (pintype "passive+no_connect"))
    )
    (net (code "186") (name "unconnected-(U14B-PI12-PadE3)") (class "Default")
      (node (ref "U14") (pin "E3") (pinfunction "PI12_E3") (pintype "passive+no_connect"))
    )
    (net (code "187") (name "unconnected-(U14B-PI13-PadG3)") (class "Default")
      (node (ref "U14") (pin "G3") (pinfunction "PI13_G3") (pintype "passive+no_connect"))
    )
    (net (code "188") (name "unconnected-(U14B-PI14-PadH3)") (class "Default")
      (node (ref "U14") (pin "H3") (pinfunction "PI14_H3") (pintype "passive+no_connect"))
    )
    (net (code "189") (name "unconnected-(U14B-PI15-PadG4)") (class "Default")
      (node (ref "U14") (pin "G4") (pinfunction "PI15_G4") (pintype "passive+no_connect"))
    )
  )
)
